# source_eagle.net
KiCad netlist of a schematic drawn in EAGLE
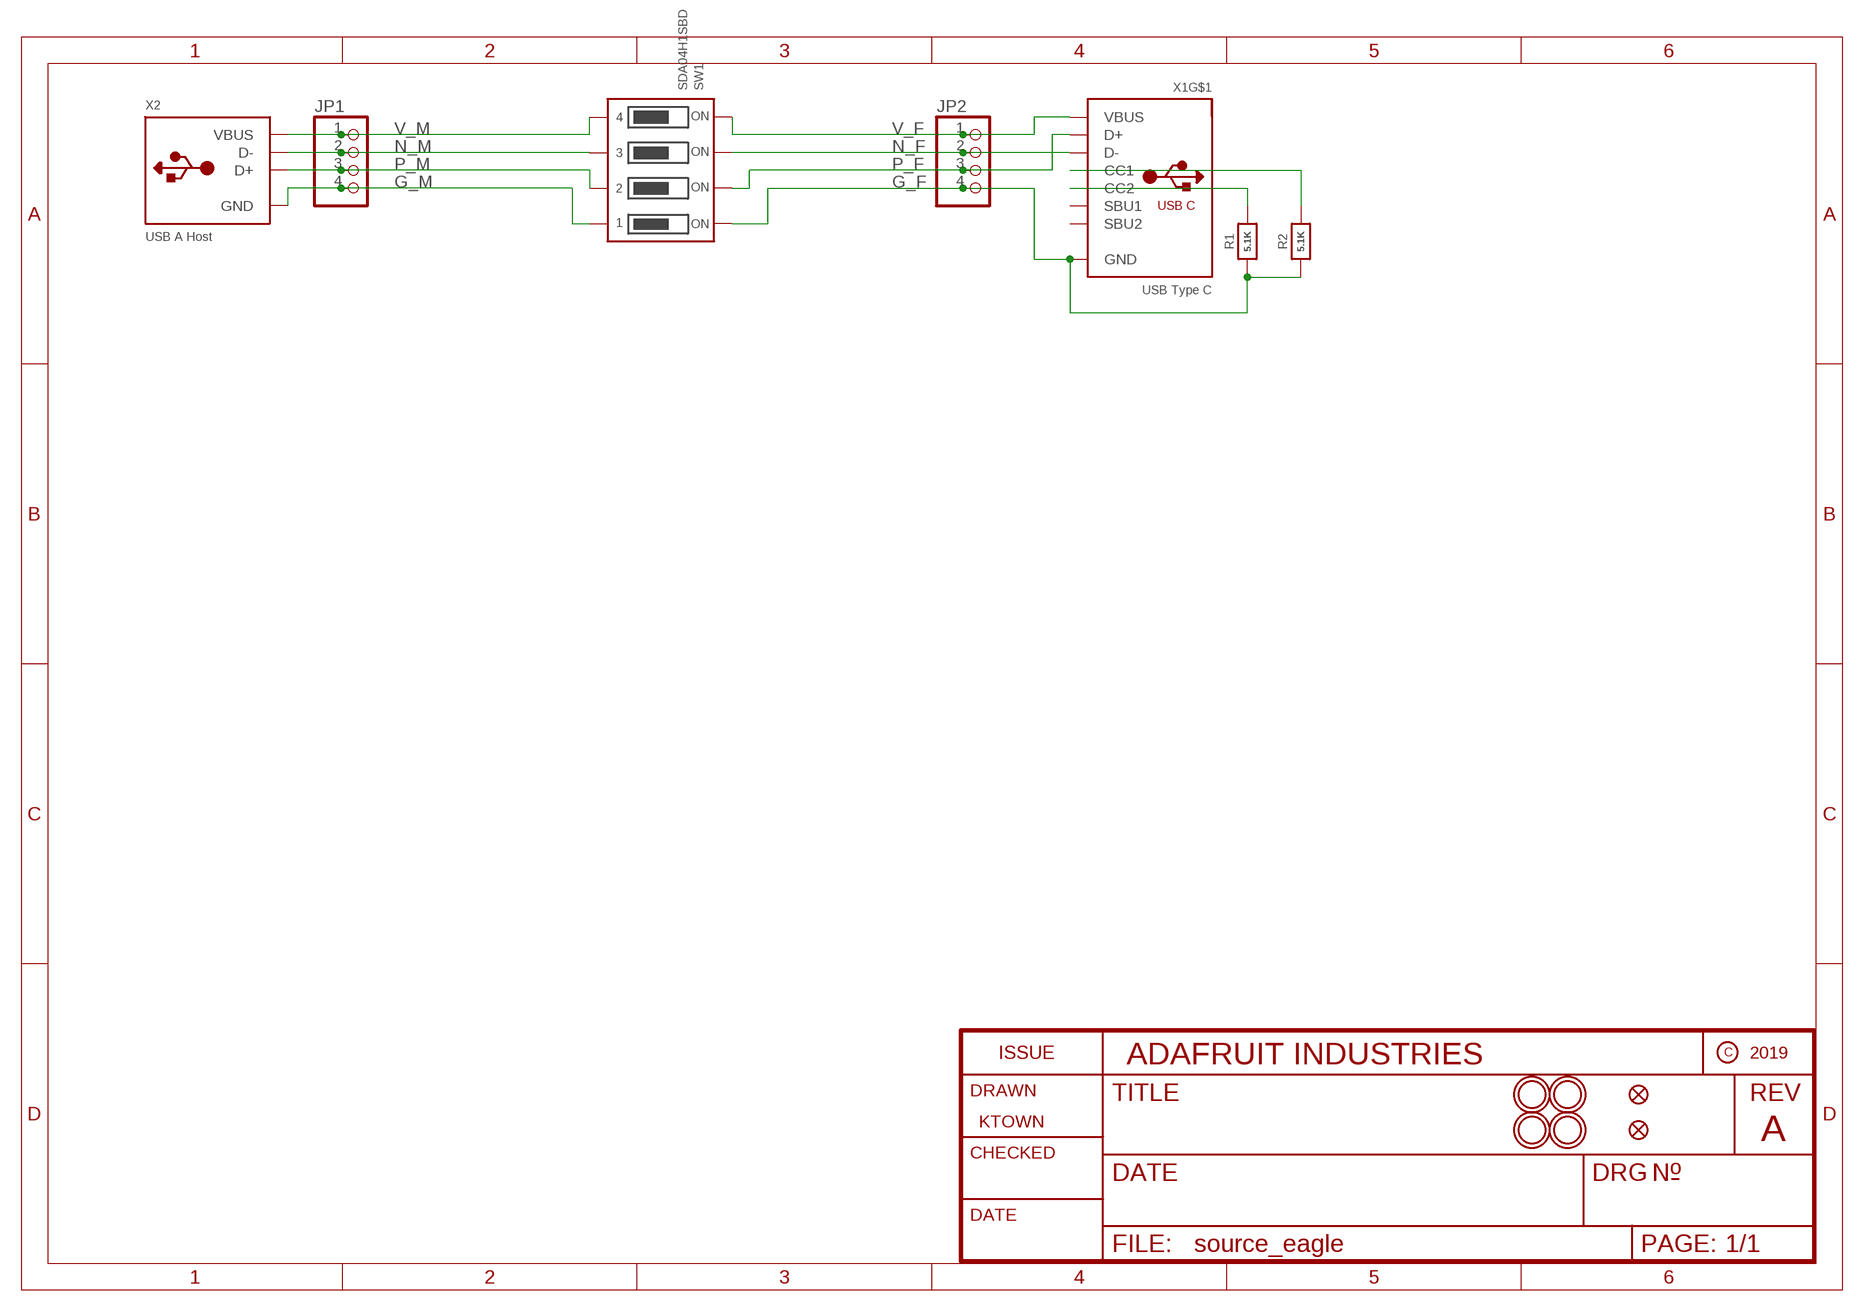
[diagram p0: schematic, sheet 1]

(export (version "E")
  (design (tool "Eeschema 10.0.6"))
  (components
    (comp (ref "FID1")
      (value "FIDUCIAL_1MM")
      (footprint "eagle-import:FIDUCIAL_1MM")
      (libsource (lib "eagle-import") (part "FIDUCIAL_1MM"))
    )
    (comp (ref "FID2")
      (value "FIDUCIAL_1MM")
      (footprint "eagle-import:FIDUCIAL_1MM")
      (libsource (lib "eagle-import") (part "FIDUCIAL_1MM"))
    )
    (comp (ref "JP1")
      (value "HEADER-1X4ROUND")
      (footprint "eagle-import:1X04_ROUND")
      (libsource (lib "eagle-import") (part "HEADER-1X4ROUND"))
    )
    (comp (ref "JP2")
      (value "HEADER-1X4ROUND")
      (footprint "eagle-import:1X04_ROUND")
      (libsource (lib "eagle-import") (part "HEADER-1X4ROUND"))
    )
    (comp (ref "R1")
      (value "5.1K")
      (footprint "eagle-import:0603-NO")
      (libsource (lib "eagle-import") (part "RESISTOR_0603_NOOUT"))
    )
    (comp (ref "R2")
      (value "5.1K")
      (footprint "eagle-import:0603-NO")
      (libsource (lib "eagle-import") (part "RESISTOR_0603_NOOUT"))
    )
    (comp (ref "SW1")
      (value "SDA04H1SBD")
      (footprint "eagle-import:DIPSWITCH_4PIN")
      (libsource (lib "eagle-import") (part "DIPSWITCH_4PIN"))
    )
    (comp (ref "U$1")
      (value "MOUNTINGHOLE2.5")
      (footprint "eagle-import:MOUNTINGHOLE_2.5_PLATED")
      (libsource (lib "eagle-import") (part "MOUNTINGHOLE2.5"))
    )
    (comp (ref "U$2")
      (value "MOUNTINGHOLE2.5")
      (footprint "eagle-import:MOUNTINGHOLE_2.5_PLATED")
      (libsource (lib "eagle-import") (part "MOUNTINGHOLE2.5"))
    )
    (comp (ref "U$3")
      (value "MOUNTINGHOLE2.5")
      (footprint "eagle-import:MOUNTINGHOLE_2.5_PLATED")
      (libsource (lib "eagle-import") (part "MOUNTINGHOLE2.5"))
    )
    (comp (ref "U$4")
      (value "MOUNTINGHOLE2.5")
      (footprint "eagle-import:MOUNTINGHOLE_2.5_PLATED")
      (libsource (lib "eagle-import") (part "MOUNTINGHOLE2.5"))
    )
    (comp (ref "X1")
      (value "USB Type C")
      (footprint "eagle-import:USB_C_CUSB31-CFM2AX-01-X")
      (libsource (lib "eagle-import") (part "USB_C"))
    )
    (comp (ref "X2")
      (value "USB A Host")
      (footprint "eagle-import:USB_HOST-PTH")
      (libsource (lib "eagle-import") (part "USB_TYPEAPTHFML"))
    )
  )
  (nets
    (net (code "1") (name "/G_F") (class "Default")
      (node (ref "JP2") (pin "4") (pinfunction "4_4") (pintype "passive"))
      (node (ref "R1") (pin "1") (pinfunction "1_1") (pintype "passive"))
      (node (ref "R2") (pin "1") (pinfunction "1_1") (pintype "passive"))
      (node (ref "SW1") (pin "1ON") (pinfunction "1ON_1ON") (pintype "bidirectional"))
      (node (ref "X1") (pin "A1B12") (pinfunction "GND_A1B12") (pintype "power_in"))
      (node (ref "X1") (pin "B1A12") (pinfunction "GND_B1A12") (pintype "power_in"))
    )
    (net (code "2") (name "/G_M") (class "Default")
      (node (ref "JP1") (pin "4") (pinfunction "4_4") (pintype "passive"))
      (node (ref "SW1") (pin "1OFF") (pinfunction "1OFF_1OFF") (pintype "bidirectional"))
      (node (ref "X2") (pin "GND") (pinfunction "GND_GND") (pintype "power_in"))
    )
    (net (code "3") (name "/N_F") (class "Default")
      (node (ref "JP2") (pin "2") (pinfunction "2_2") (pintype "passive"))
      (node (ref "SW1") (pin "3ON") (pinfunction "3ON_3ON") (pintype "bidirectional"))
      (node (ref "X1") (pin "A7") (pinfunction "D-_A7") (pintype "bidirectional"))
      (node (ref "X1") (pin "B7") (pinfunction "D-_B7") (pintype "bidirectional"))
    )
    (net (code "4") (name "/N_M") (class "Default")
      (node (ref "JP1") (pin "2") (pinfunction "2_2") (pintype "passive"))
      (node (ref "SW1") (pin "3OFF") (pinfunction "3OFF_3OFF") (pintype "bidirectional"))
      (node (ref "X2") (pin "D-") (pinfunction "D-_D-") (pintype "bidirectional"))
    )
    (net (code "5") (name "/P_F") (class "Default")
      (node (ref "JP2") (pin "3") (pinfunction "3_3") (pintype "passive"))
      (node (ref "SW1") (pin "2ON") (pinfunction "2ON_2ON") (pintype "bidirectional"))
      (node (ref "X1") (pin "A6") (pinfunction "D+_A6") (pintype "bidirectional"))
      (node (ref "X1") (pin "B6") (pinfunction "D+_B6") (pintype "bidirectional"))
    )
    (net (code "6") (name "/P_M") (class "Default")
      (node (ref "JP1") (pin "3") (pinfunction "3_3") (pintype "passive"))
      (node (ref "SW1") (pin "2OFF") (pinfunction "2OFF_2OFF") (pintype "bidirectional"))
      (node (ref "X2") (pin "D+") (pinfunction "D+_D+") (pintype "bidirectional"))
    )
    (net (code "7") (name "/V_F") (class "Default")
      (node (ref "JP2") (pin "1") (pinfunction "1_1") (pintype "passive"))
      (node (ref "SW1") (pin "4ON") (pinfunction "4ON_4ON") (pintype "bidirectional"))
      (node (ref "X1") (pin "A4B9") (pinfunction "VBUS_A4B9") (pintype "power_in"))
      (node (ref "X1") (pin "B4A9") (pinfunction "VBUS_B4A9") (pintype "power_in"))
    )
    (net (code "8") (name "/V_M") (class "Default")
      (node (ref "JP1") (pin "1") (pinfunction "1_1") (pintype "passive"))
      (node (ref "SW1") (pin "4OFF") (pinfunction "4OFF_4OFF") (pintype "bidirectional"))
      (node (ref "X2") (pin "VBUS") (pinfunction "VBUS_VBUS") (pintype "power_in"))
    )
    (net (code "9") (name "Net-(X1A-CC1)") (class "Default")
      (node (ref "R2") (pin "2") (pinfunction "2_2") (pintype "passive"))
      (node (ref "X1") (pin "A5") (pinfunction "CC1_A5") (pintype "bidirectional"))
    )
    (net (code "10") (name "Net-(X1A-CC2)") (class "Default")
      (node (ref "R1") (pin "2") (pinfunction "2_2") (pintype "passive"))
      (node (ref "X1") (pin "B5") (pinfunction "CC2_B5") (pintype "bidirectional"))
    )
    (net (code "11") (name "unconnected-(X1A-SBU1-PadA8)") (class "Default")
      (node (ref "X1") (pin "A8") (pinfunction "SBU1_A8") (pintype "bidirectional"))
    )
    (net (code "12") (name "unconnected-(X1A-SBU2-PadB8)") (class "Default")
      (node (ref "X1") (pin "B8") (pinfunction "SBU2_B8") (pintype "bidirectional"))
    )
  )
)
